# Sheet1.net
KiCad netlist of a schematic drawn in Altium Designer
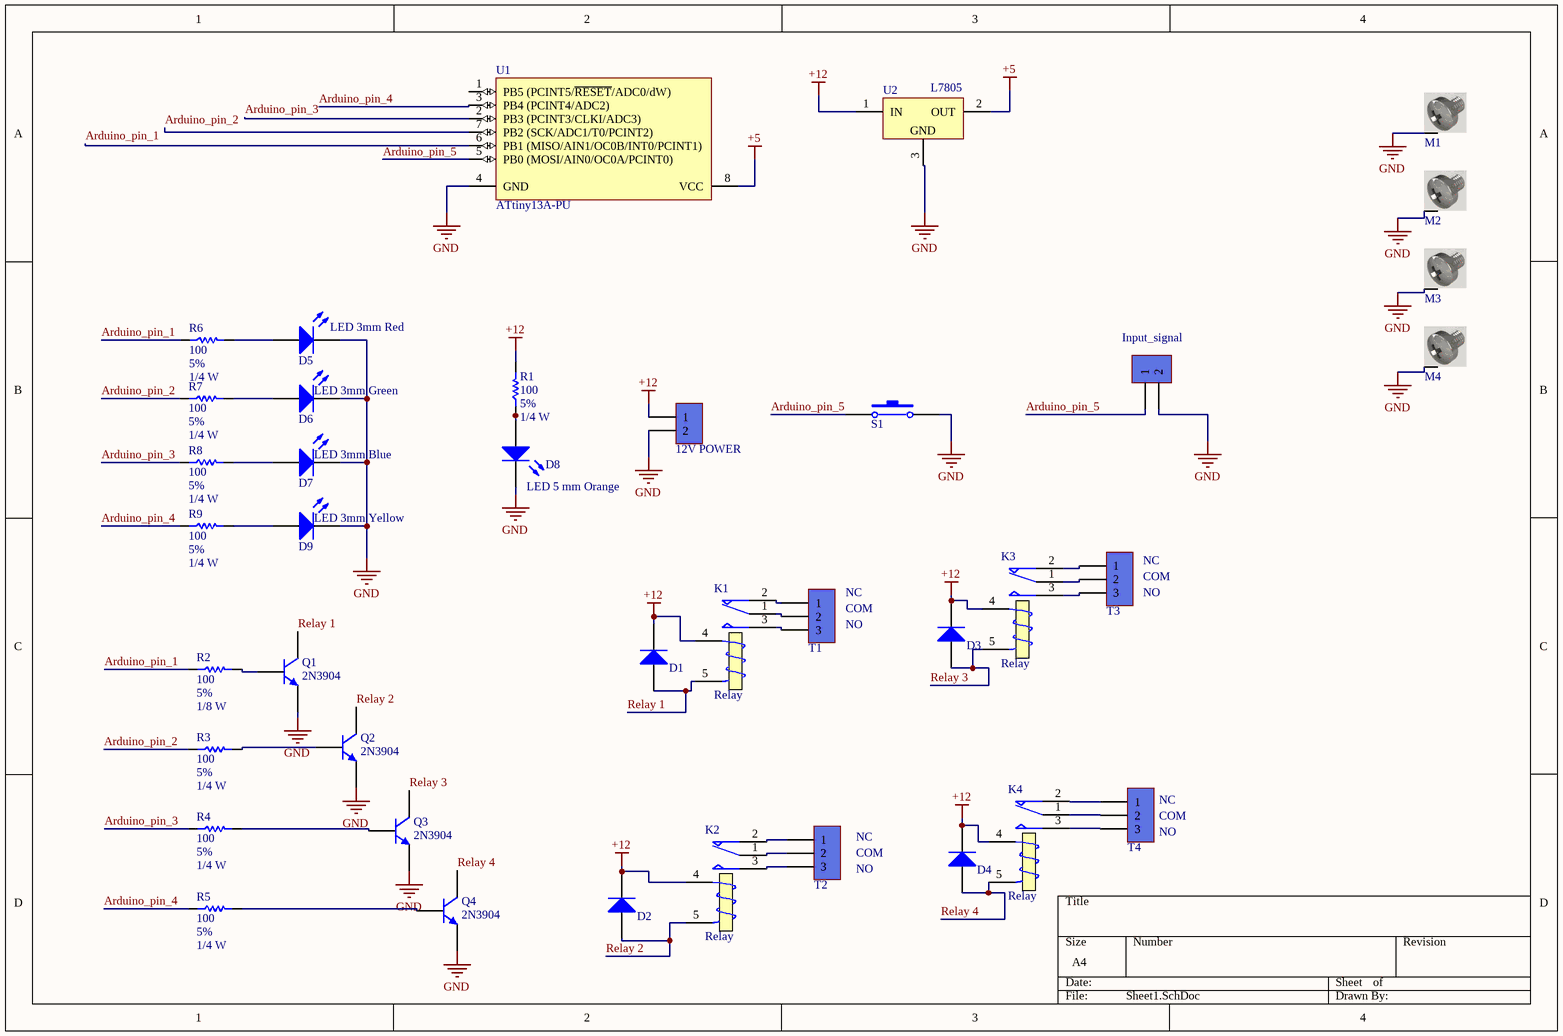
[diagram p0: Sheet1.SchDoc]

(export (version "E")
  (design (tool "Eeschema 10.0.6"))
  (components
    (comp (ref "12V POWER")
      (value "Terminal")
      (footprint "Terminal 1*2")
      (description "Terminal 2 Pin 250VAC 16A")
      (fields (field (name "DESIGNER") "Seyed Mohsen Ghasemain") (field (name "E-MAIL") "picpars@gmail.com"))
      (libsource (lib "") (part "Terminal 1*2_1"))
    )
    (comp (ref "D1")
      (value "Diode 1N4007 vertical")
      (footprint "D 50mm")
      (description "1 Amp General Purpose Rectifier")
      (fields (field (name "PUBLISHER") "seyed mohsen ghasemian"))
      (libsource (lib "usefully_Library") (part "Diode 1N4007 vertical"))
    )
    (comp (ref "D2")
      (value "Diode 1N4007 vertical")
      (footprint "D 50mm")
      (description "1 Amp General Purpose Rectifier")
      (fields (field (name "PUBLISHER") "seyed mohsen ghasemian"))
      (libsource (lib "usefully_Library") (part "Diode 1N4007 vertical"))
    )
    (comp (ref "D3")
      (value "Diode 1N4007 vertical")
      (footprint "D 50mm")
      (description "1 Amp General Purpose Rectifier")
      (fields (field (name "PUBLISHER") "seyed mohsen ghasemian"))
      (libsource (lib "usefully_Library") (part "Diode 1N4007 vertical"))
    )
    (comp (ref "D4")
      (value "Diode 1N4007 vertical")
      (footprint "D 50mm")
      (description "1 Amp General Purpose Rectifier")
      (fields (field (name "PUBLISHER") "seyed mohsen ghasemian"))
      (libsource (lib "usefully_Library") (part "Diode 1N4007 vertical"))
    )
    (comp (ref "D5")
      (value "LED 3mm Red")
      (footprint "LED-3mm")
      (description "Typical LED")
      (fields (field (name "DESIGNER") "Seyed Mohsen Ghasemian") (field (name "PUBLISHER") "www.picpars.com"))
      (libsource (lib "usefully_Library") (part "LED 3mm"))
    )
    (comp (ref "D6")
      (value "LED 3mm Green")
      (footprint "LED-3mm")
      (description "Typical LED")
      (fields (field (name "DESIGNER") "Seyed Mohsen Ghasemian") (field (name "PUBLISHER") "www.picpars.com"))
      (libsource (lib "usefully_Library") (part "LED 3mm"))
    )
    (comp (ref "D7")
      (value "LED 3mm Blue")
      (footprint "LED-3mm")
      (description "Typical LED")
      (fields (field (name "DESIGNER") "Seyed Mohsen Ghasemian") (field (name "PUBLISHER") "www.picpars.com"))
      (libsource (lib "usefully_Library") (part "LED 3mm"))
    )
    (comp (ref "D8")
      (value "LED 5 mm Orange")
      (footprint "LED-3mm")
      (description "Typical LED")
      (fields (field (name "DESIGNER") "Seyed Mohsen Ghasemian") (field (name "PUBLISHER") "www.picpars.com"))
      (libsource (lib "usefully_Library") (part "LED 3mm"))
    )
    (comp (ref "D9")
      (value "LED 3mm Yellow")
      (footprint "LED-3mm")
      (description "Typical LED")
      (fields (field (name "DESIGNER") "Seyed Mohsen Ghasemian") (field (name "PUBLISHER") "www.picpars.com"))
      (libsource (lib "usefully_Library") (part "LED 3mm"))
    )
    (comp (ref "Input_signal")
      (value "Terminal")
      (footprint "Terminal 1*2")
      (description "Terminal 2 Pin 250VAC 16A")
      (fields (field (name "DESIGNER") "Seyed Mohsen Ghasemain") (field (name "E-MAIL") "picpars@gmail.com"))
      (libsource (lib "usefully_Library") (part "Terminal 1*2"))
    )
    (comp (ref "K1")
      (value "Relay")
      (footprint "Relay 15.40x12.10x13.10")
      (description "SPDT Relay")
      (fields (field (name "DESIGNER") "Eng. Saeid Jorablo"))
      (libsource (lib "My_Library") (part "Relay"))
    )
    (comp (ref "K2")
      (value "Relay")
      (footprint "Relay 15.40x12.10x13.10")
      (description "SPDT Relay")
      (fields (field (name "DESIGNER") "Eng. Saeid Jorablo"))
      (libsource (lib "My_Library") (part "Relay"))
    )
    (comp (ref "K3")
      (value "Relay")
      (footprint "Relay 15.40x12.10x13.10")
      (description "SPDT Relay")
      (fields (field (name "DESIGNER") "Eng. Saeid Jorablo"))
      (libsource (lib "My_Library") (part "Relay"))
    )
    (comp (ref "K4")
      (value "Relay")
      (footprint "Relay 15.40x12.10x13.10")
      (description "SPDT Relay")
      (fields (field (name "DESIGNER") "Eng. Saeid Jorablo"))
      (libsource (lib "My_Library") (part "Relay"))
    )
    (comp (ref "M1")
      (value "Screw")
      (footprint "Board Screw")
      (description "Board Screw With Spacer")
      (libsource (lib "My_Library") (part "Board Screw"))
    )
    (comp (ref "M2")
      (value "Screw")
      (footprint "Board Screw")
      (description "Board Screw With Spacer")
      (libsource (lib "My_Library") (part "Board Screw"))
    )
    (comp (ref "M3")
      (value "Screw")
      (footprint "Board Screw")
      (description "Board Screw With Spacer")
      (libsource (lib "My_Library") (part "Board Screw"))
    )
    (comp (ref "M4")
      (value "Screw")
      (footprint "Board Screw")
      (description "Board Screw With Spacer")
      (libsource (lib "My_Library") (part "Board Screw"))
    )
    (comp (ref "Q1")
      (value "2N3904")
      (footprint "2N3904 TO92")
      (description "npn")
      (fields (field (name "MANUFACTURER") "ONSemiconductor"))
      (libsource (lib "2N3904") (part "2N3904"))
    )
    (comp (ref "Q2")
      (value "2N3904")
      (footprint "2N3904 TO92")
      (description "npn")
      (fields (field (name "MANUFACTURER") "ONSemiconductor"))
      (libsource (lib "2N3904") (part "2N3904"))
    )
    (comp (ref "Q3")
      (value "2N3904")
      (footprint "2N3904 TO92")
      (description "npn")
      (fields (field (name "MANUFACTURER") "ONSemiconductor"))
      (libsource (lib "2N3904") (part "2N3904"))
    )
    (comp (ref "Q4")
      (value "2N3904")
      (footprint "2N3904 TO92")
      (description "npn")
      (fields (field (name "MANUFACTURER") "ONSemiconductor"))
      (libsource (lib "2N3904") (part "2N3904"))
    )
    (comp (ref "R1")
      (value "100")
      (footprint "Res-(1/4)")
      (description "Resistor")
      (fields (field (name "TOLERANCE") "5%") (field (name "POWER") "1/4 W"))
      (libsource (lib "My_Library") (part "Resistor"))
    )
    (comp (ref "R2")
      (value "100")
      (footprint "Res-(1/4)")
      (description "Resistor")
      (fields (field (name "TOLERANCE") "5%") (field (name "POWER") "1/8 W"))
      (libsource (lib "My_Library") (part "Resistor"))
    )
    (comp (ref "R3")
      (value "100")
      (footprint "Res-(1/4)")
      (description "Resistor")
      (fields (field (name "TOLERANCE") "5%") (field (name "POWER") "1/4 W"))
      (libsource (lib "My_Library") (part "Resistor"))
    )
    (comp (ref "R4")
      (value "100")
      (footprint "Res-(1/4)")
      (description "Resistor")
      (fields (field (name "TOLERANCE") "5%") (field (name "POWER") "1/4 W"))
      (libsource (lib "My_Library") (part "Resistor"))
    )
    (comp (ref "R5")
      (value "100")
      (footprint "Res-(1/4)")
      (description "Resistor")
      (fields (field (name "TOLERANCE") "5%") (field (name "POWER") "1/4 W"))
      (libsource (lib "My_Library") (part "Resistor"))
    )
    (comp (ref "R6")
      (value "100")
      (footprint "Res-(1/4)")
      (description "Resistor")
      (fields (field (name "TOLERANCE") "5%") (field (name "POWER") "1/4 W"))
      (libsource (lib "My_Library") (part "Resistor"))
    )
    (comp (ref "R7")
      (value "100")
      (footprint "Res-(1/4)")
      (description "Resistor")
      (fields (field (name "TOLERANCE") "5%") (field (name "POWER") "1/4 W"))
      (libsource (lib "My_Library") (part "Resistor"))
    )
    (comp (ref "R8")
      (value "100")
      (footprint "Res-(1/4)")
      (description "Resistor")
      (fields (field (name "TOLERANCE") "5%") (field (name "POWER") "1/4 W"))
      (libsource (lib "My_Library") (part "Resistor"))
    )
    (comp (ref "R9")
      (value "100")
      (footprint "Res-(1/4)")
      (description "Resistor")
      (fields (field (name "TOLERANCE") "5%") (field (name "POWER") "1/4 W"))
      (libsource (lib "My_Library") (part "Resistor"))
    )
    (comp (ref "S1")
      (value "PB-2pin")
      (footprint "PB-2pin")
      (description "Switch")
      (fields
        (field (name "PUBLISHER") "www.picpars.com")
        (field (name "E-MAIL") "picpars@gmail.com")
        (field (name "DESIGNER") "Seyed Mohsen Ghasemian")
      )
      (libsource (lib "usefully_Library") (part "PB-2pin"))
    )
    (comp (ref "T1")
      (value "Terminal")
      (footprint "Terminal 1*3")
      (description "Terminal 3 Pin 250VAC 16A")
      (fields (field (name "DESIGNER") "Seyed Mohsen Ghasemain") (field (name "E-MAIL") "picpars@gmail.com"))
      (libsource (lib "usefully_Library") (part "Terminal 1*3"))
    )
    (comp (ref "T2")
      (value "Terminal")
      (footprint "Terminal 1*3")
      (description "Terminal 3 Pin 250VAC 16A")
      (fields (field (name "DESIGNER") "Seyed Mohsen Ghasemain") (field (name "E-MAIL") "picpars@gmail.com"))
      (libsource (lib "usefully_Library") (part "Terminal 1*3"))
    )
    (comp (ref "T3")
      (value "Terminal")
      (footprint "Terminal 1*3")
      (description "Terminal 3 Pin 250VAC 16A")
      (fields (field (name "DESIGNER") "Seyed Mohsen Ghasemain") (field (name "E-MAIL") "picpars@gmail.com"))
      (libsource (lib "usefully_Library") (part "Terminal 1*3"))
    )
    (comp (ref "T4")
      (value "Terminal")
      (footprint "Terminal 1*3")
      (description "Terminal 3 Pin 250VAC 16A")
      (fields (field (name "DESIGNER") "Seyed Mohsen Ghasemain") (field (name "E-MAIL") "picpars@gmail.com"))
      (libsource (lib "usefully_Library") (part "Terminal 1*3"))
    )
    (comp (ref "U1")
      (value "ATtiny13A-PU")
      (footprint "ATtiny13A-PU 8P3")
      (libsource (lib "ATtiny13A-PU") (part "ATtiny13A-PU"))
    )
    (comp (ref "U2")
      (value "L7805")
      (footprint "78XXCV - Right")
      (description "Fixed Voltage Regulator")
      (fields (field (name "DESIGNER") "Saeid Jorablo"))
      (libsource (lib "My_Library") (part "L78XXCV"))
    )
  )
  (nets
    (net (code "1") (name "+5") (class "Default")
      (node (ref "U1") (pin "8") (pinfunction "VCC_8") (pintype "power_in"))
      (node (ref "U2") (pin "2") (pinfunction "OUT_2") (pintype "passive"))
    )
    (net (code "2") (name "+12") (class "Default")
      (node (ref "12V POWER") (pin "1") (pinfunction "1_1") (pintype "passive"))
      (node (ref "D1") (pin "2") (pinfunction "K_2") (pintype "passive"))
      (node (ref "D2") (pin "2") (pinfunction "K_2") (pintype "passive"))
      (node (ref "D3") (pin "2") (pinfunction "K_2") (pintype "passive"))
      (node (ref "D4") (pin "2") (pinfunction "K_2") (pintype "passive"))
      (node (ref "K1") (pin "4") (pinfunction "T1_4") (pintype "passive"))
      (node (ref "K2") (pin "4") (pinfunction "T1_4") (pintype "passive"))
      (node (ref "K3") (pin "4") (pinfunction "T1_4") (pintype "passive"))
      (node (ref "K4") (pin "4") (pinfunction "T1_4") (pintype "passive"))
      (node (ref "R1") (pin "2") (pinfunction "2_2") (pintype "passive"))
      (node (ref "U2") (pin "1") (pinfunction "IN_1") (pintype "passive"))
    )
    (net (code "3") (name "/Arduino_pin_1") (class "Default")
      (node (ref "R2") (pin "1") (pinfunction "1_1") (pintype "passive"))
      (node (ref "R6") (pin "1") (pinfunction "1_1") (pintype "passive"))
      (node (ref "U1") (pin "6") (pinfunction "PB1_(MISO/AIN1/OC0B/INT0/PCINT1)_6") (pintype "bidirectional"))
    )
    (net (code "4") (name "/Arduino_pin_2") (class "Default")
      (node (ref "R3") (pin "1") (pinfunction "1_1") (pintype "passive"))
      (node (ref "R7") (pin "1") (pinfunction "1_1") (pintype "passive"))
      (node (ref "U1") (pin "7") (pinfunction "PB2_(SCK/ADC1/T0/PCINT2)_7") (pintype "bidirectional"))
    )
    (net (code "5") (name "/Arduino_pin_3") (class "Default")
      (node (ref "R4") (pin "1") (pinfunction "1_1") (pintype "passive"))
      (node (ref "R8") (pin "1") (pinfunction "1_1") (pintype "passive"))
      (node (ref "U1") (pin "2") (pinfunction "PB3_(PCINT3/CLKI/ADC3)_2") (pintype "bidirectional"))
    )
    (net (code "6") (name "/Arduino_pin_4") (class "Default")
      (node (ref "R5") (pin "1") (pinfunction "1_1") (pintype "passive"))
      (node (ref "R9") (pin "1") (pinfunction "1_1") (pintype "passive"))
      (node (ref "U1") (pin "3") (pinfunction "PB4_(PCINT4/ADC2)_3") (pintype "bidirectional"))
    )
    (net (code "7") (name "/Arduino_pin_5") (class "Default")
      (node (ref "Input_signal") (pin "1") (pinfunction "1_1") (pintype "passive"))
      (node (ref "S1") (pin "1") (pinfunction "1_1") (pintype "passive"))
      (node (ref "U1") (pin "5") (pinfunction "PB0_(MOSI/AIN0/OC0A/PCINT0)_5") (pintype "bidirectional"))
    )
    (net (code "8") (name "/Relay 1") (class "Default")
      (node (ref "D1") (pin "1") (pinfunction "A_1") (pintype "passive"))
      (node (ref "K1") (pin "5") (pinfunction "T2_5") (pintype "passive"))
      (node (ref "Q1") (pin "3") (pinfunction "C_3") (pintype "passive"))
    )
    (net (code "9") (name "/Relay 2") (class "Default")
      (node (ref "D2") (pin "1") (pinfunction "A_1") (pintype "passive"))
      (node (ref "K2") (pin "5") (pinfunction "T2_5") (pintype "passive"))
      (node (ref "Q2") (pin "3") (pinfunction "C_3") (pintype "passive"))
    )
    (net (code "10") (name "/Relay 3") (class "Default")
      (node (ref "D3") (pin "1") (pinfunction "A_1") (pintype "passive"))
      (node (ref "K3") (pin "5") (pinfunction "T2_5") (pintype "passive"))
      (node (ref "Q3") (pin "3") (pinfunction "C_3") (pintype "passive"))
    )
    (net (code "11") (name "/Relay 4") (class "Default")
      (node (ref "D4") (pin "1") (pinfunction "A_1") (pintype "passive"))
      (node (ref "K4") (pin "5") (pinfunction "T2_5") (pintype "passive"))
      (node (ref "Q4") (pin "3") (pinfunction "C_3") (pintype "passive"))
    )
    (net (code "12") (name "GND") (class "Default")
      (node (ref "12V POWER") (pin "2") (pinfunction "2_2") (pintype "passive"))
      (node (ref "D5") (pin "2") (pinfunction "K_2") (pintype "passive"))
      (node (ref "D6") (pin "2") (pinfunction "K_2") (pintype "passive"))
      (node (ref "D7") (pin "2") (pinfunction "K_2") (pintype "passive"))
      (node (ref "D8") (pin "2") (pinfunction "K_2") (pintype "passive"))
      (node (ref "D9") (pin "2") (pinfunction "K_2") (pintype "passive"))
      (node (ref "Input_signal") (pin "2") (pinfunction "2_2") (pintype "passive"))
      (node (ref "M1") (pin "S") (pinfunction "S_S") (pintype "passive"))
      (node (ref "M2") (pin "S") (pinfunction "S_S") (pintype "passive"))
      (node (ref "M3") (pin "S") (pinfunction "S_S") (pintype "passive"))
      (node (ref "M4") (pin "S") (pinfunction "S_S") (pintype "passive"))
      (node (ref "Q1") (pin "1") (pinfunction "E_1") (pintype "passive"))
      (node (ref "Q2") (pin "1") (pinfunction "E_1") (pintype "passive"))
      (node (ref "Q3") (pin "1") (pinfunction "E_1") (pintype "passive"))
      (node (ref "Q4") (pin "1") (pinfunction "E_1") (pintype "passive"))
      (node (ref "S1") (pin "2") (pinfunction "2_2") (pintype "passive"))
      (node (ref "U1") (pin "4") (pinfunction "GND_4") (pintype "power_in"))
      (node (ref "U2") (pin "3") (pinfunction "GND_3") (pintype "passive"))
    )
    (net (code "13") (name "Net-(D5-A)") (class "Default")
      (node (ref "D5") (pin "1") (pinfunction "A_1") (pintype "passive"))
      (node (ref "R6") (pin "2") (pinfunction "2_2") (pintype "passive"))
    )
    (net (code "14") (name "Net-(D6-A)") (class "Default")
      (node (ref "D6") (pin "1") (pinfunction "A_1") (pintype "passive"))
      (node (ref "R7") (pin "2") (pinfunction "2_2") (pintype "passive"))
    )
    (net (code "15") (name "Net-(D7-A)") (class "Default")
      (node (ref "D7") (pin "1") (pinfunction "A_1") (pintype "passive"))
      (node (ref "R8") (pin "2") (pinfunction "2_2") (pintype "passive"))
    )
    (net (code "16") (name "Net-(D8-A)") (class "Default")
      (node (ref "D8") (pin "1") (pinfunction "A_1") (pintype "passive"))
      (node (ref "R1") (pin "1") (pinfunction "1_1") (pintype "passive"))
    )
    (net (code "17") (name "Net-(D9-A)") (class "Default")
      (node (ref "D9") (pin "1") (pinfunction "A_1") (pintype "passive"))
      (node (ref "R9") (pin "2") (pinfunction "2_2") (pintype "passive"))
    )
    (net (code "18") (name "Net-(K1-COM)") (class "Default")
      (node (ref "K1") (pin "1") (pinfunction "COM_1") (pintype "passive"))
      (node (ref "T1") (pin "2") (pinfunction "2_2") (pintype "passive"))
    )
    (net (code "19") (name "Net-(K1-NC)") (class "Default")
      (node (ref "K1") (pin "2") (pinfunction "NC_2") (pintype "passive"))
      (node (ref "T1") (pin "1") (pinfunction "1_1") (pintype "passive"))
    )
    (net (code "20") (name "Net-(K1-NO)") (class "Default")
      (node (ref "K1") (pin "3") (pinfunction "NO_3") (pintype "passive"))
      (node (ref "T1") (pin "3") (pinfunction "3_3") (pintype "passive"))
    )
    (net (code "21") (name "Net-(K2-COM)") (class "Default")
      (node (ref "K2") (pin "1") (pinfunction "COM_1") (pintype "passive"))
      (node (ref "T2") (pin "2") (pinfunction "2_2") (pintype "passive"))
    )
    (net (code "22") (name "Net-(K2-NC)") (class "Default")
      (node (ref "K2") (pin "2") (pinfunction "NC_2") (pintype "passive"))
      (node (ref "T2") (pin "1") (pinfunction "1_1") (pintype "passive"))
    )
    (net (code "23") (name "Net-(K2-NO)") (class "Default")
      (node (ref "K2") (pin "3") (pinfunction "NO_3") (pintype "passive"))
      (node (ref "T2") (pin "3") (pinfunction "3_3") (pintype "passive"))
    )
    (net (code "24") (name "Net-(K3-COM)") (class "Default")
      (node (ref "K3") (pin "1") (pinfunction "COM_1") (pintype "passive"))
      (node (ref "T3") (pin "2") (pinfunction "2_2") (pintype "passive"))
    )
    (net (code "25") (name "Net-(K3-NC)") (class "Default")
      (node (ref "K3") (pin "2") (pinfunction "NC_2") (pintype "passive"))
      (node (ref "T3") (pin "1") (pinfunction "1_1") (pintype "passive"))
    )
    (net (code "26") (name "Net-(K3-NO)") (class "Default")
      (node (ref "K3") (pin "3") (pinfunction "NO_3") (pintype "passive"))
      (node (ref "T3") (pin "3") (pinfunction "3_3") (pintype "passive"))
    )
    (net (code "27") (name "Net-(K4-COM)") (class "Default")
      (node (ref "K4") (pin "1") (pinfunction "COM_1") (pintype "passive"))
      (node (ref "T4") (pin "2") (pinfunction "2_2") (pintype "passive"))
    )
    (net (code "28") (name "Net-(K4-NC)") (class "Default")
      (node (ref "K4") (pin "2") (pinfunction "NC_2") (pintype "passive"))
      (node (ref "T4") (pin "1") (pinfunction "1_1") (pintype "passive"))
    )
    (net (code "29") (name "Net-(K4-NO)") (class "Default")
      (node (ref "K4") (pin "3") (pinfunction "NO_3") (pintype "passive"))
      (node (ref "T4") (pin "3") (pinfunction "3_3") (pintype "passive"))
    )
    (net (code "30") (name "Net-(Q1-B)") (class "Default")
      (node (ref "Q1") (pin "2") (pinfunction "B_2") (pintype "passive"))
      (node (ref "R2") (pin "2") (pinfunction "2_2") (pintype "passive"))
    )
    (net (code "31") (name "Net-(Q2-B)") (class "Default")
      (node (ref "Q2") (pin "2") (pinfunction "B_2") (pintype "passive"))
      (node (ref "R3") (pin "2") (pinfunction "2_2") (pintype "passive"))
    )
    (net (code "32") (name "Net-(Q3-B)") (class "Default")
      (node (ref "Q3") (pin "2") (pinfunction "B_2") (pintype "passive"))
      (node (ref "R4") (pin "2") (pinfunction "2_2") (pintype "passive"))
    )
    (net (code "33") (name "Net-(Q4-B)") (class "Default")
      (node (ref "Q4") (pin "2") (pinfunction "B_2") (pintype "passive"))
      (node (ref "R5") (pin "2") (pinfunction "2_2") (pintype "passive"))
    )
    (net (code "34") (name "unconnected-(U1-PB5_(PCINT5{slash}~{RESET}{slash}ADC0{slash}dW)-Pad1)") (class "Default")
      (node (ref "U1") (pin "1") (pinfunction "PB5_(PCINT5/~{RESET}/ADC0/dW)_1") (pintype "bidirectional"))
    )
  )
)
